# Shift_Register_Test_Board.net
KiCad netlist of a schematic drawn in Altium Designer
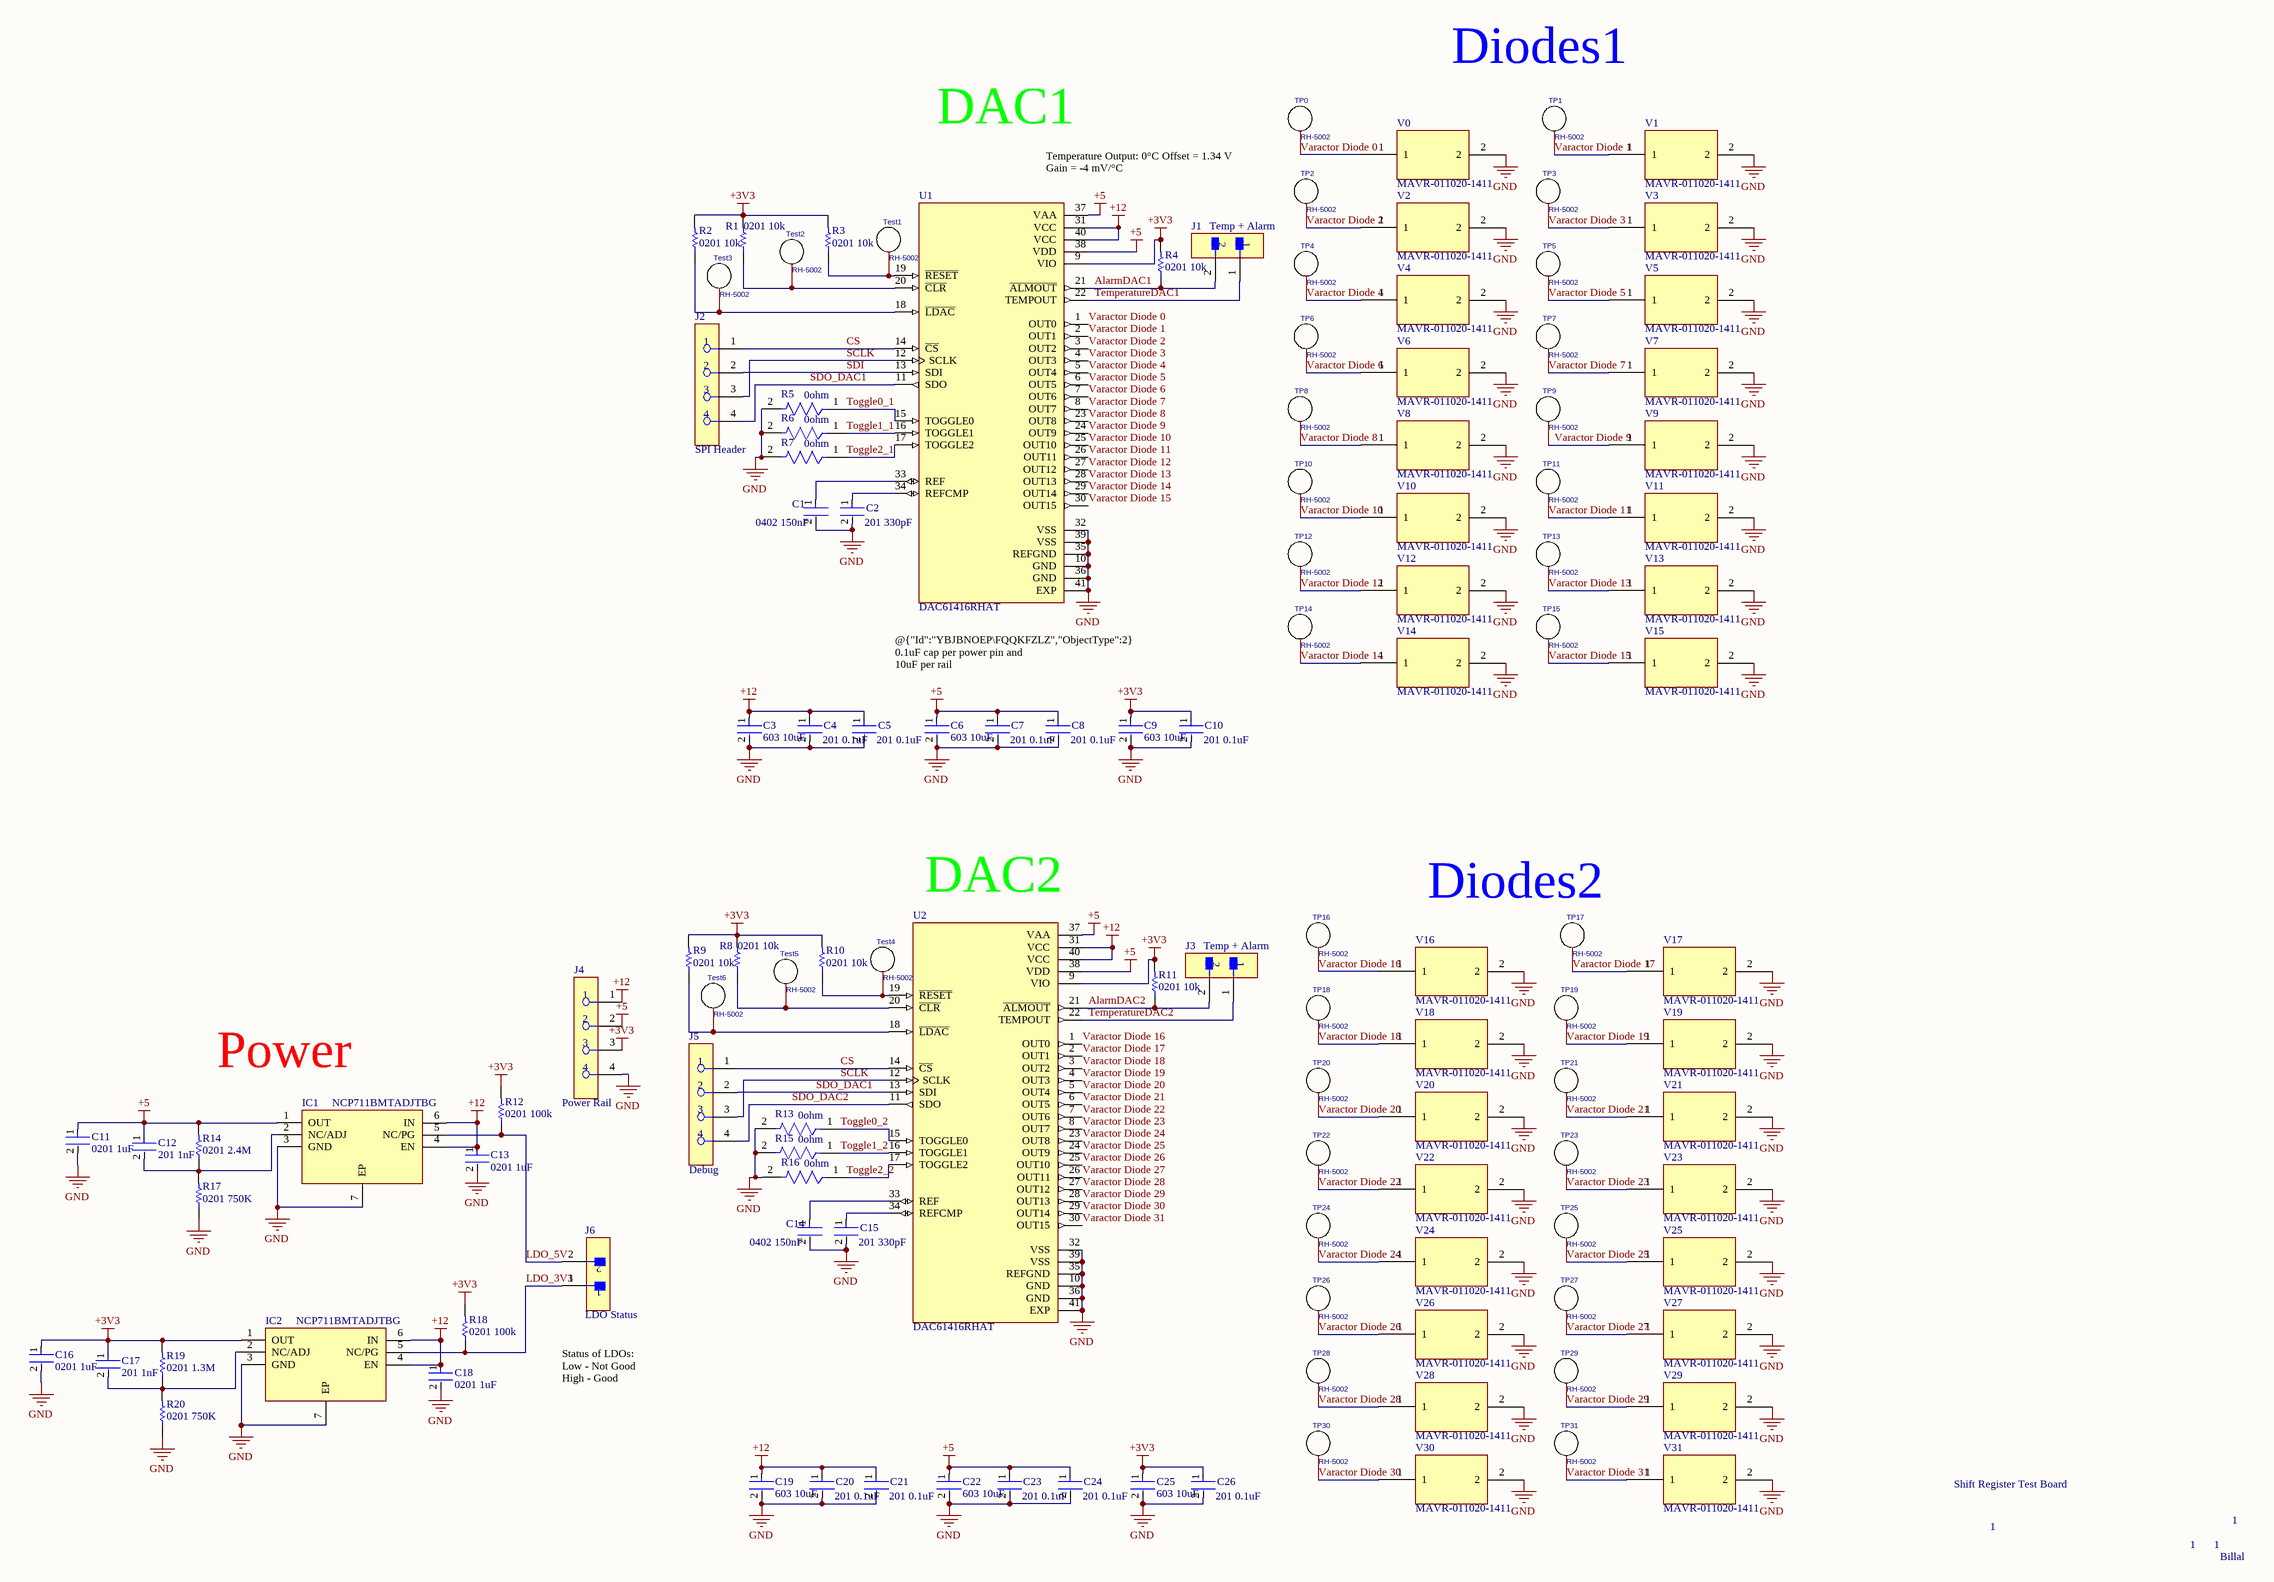
[diagram p0: Shift Register Test Board.SchDoc]

(export (version "E")
  (design (tool "Eeschema 10.0.6"))
  (components
    (comp (ref "C1")
      (value "0402 150nF")
      (footprint "FP-GRM155-0_1-IPC_C")
      (description "C5448879")
      (libsource (lib "Altium Content Vault") (part "11868f565c42a9108669ba33697ecf6"))
    )
    (comp (ref "C2")
      (value "201 330pF")
      (footprint "FP-GRM033-0_09-IPC_A")
      (description "C3899460")
      (fields (field (name "TOLERANCE") "20%"))
      (libsource (lib "Altium Content Vault") (part "02cd4be3c70576c341d710602a673aa"))
    )
    (comp (ref "C3")
      (value "603 10uF")
      (footprint "FP-C0603C106M8PACTU-MFG")
      (description "C194427")
      (libsource (lib "Altium Content Vault") (part "02cd4be3c70576c341d710602a673aa"))
    )
    (comp (ref "C4")
      (value "201 0.1uF")
      (footprint "FP-GRM033-0_09-IPC_A")
      (description "C181043")
      (fields (field (name "TOLERANCE") "20%"))
      (libsource (lib "Altium Content Vault") (part "02cd4be3c70576c341d710602a673aa"))
    )
    (comp (ref "C5")
      (value "201 0.1uF")
      (footprint "FP-GRM033-0_09-IPC_A")
      (description "C181043")
      (fields (field (name "TOLERANCE") "20%"))
      (libsource (lib "Altium Content Vault") (part "02cd4be3c70576c341d710602a673aa"))
    )
    (comp (ref "C6")
      (value "603 10uF")
      (footprint "FP-C0603C106M8PACTU-MFG")
      (description "C194427")
      (libsource (lib "Altium Content Vault") (part "02cd4be3c70576c341d710602a673aa"))
    )
    (comp (ref "C7")
      (value "201 0.1uF")
      (footprint "FP-GRM033-0_09-IPC_A")
      (description "C181043")
      (fields (field (name "TOLERANCE") "20%"))
      (libsource (lib "Altium Content Vault") (part "02cd4be3c70576c341d710602a673aa"))
    )
    (comp (ref "C8")
      (value "201 0.1uF")
      (footprint "FP-GRM033-0_09-IPC_A")
      (description "C181043")
      (fields (field (name "TOLERANCE") "20%"))
      (libsource (lib "Altium Content Vault") (part "02cd4be3c70576c341d710602a673aa"))
    )
    (comp (ref "C9")
      (value "603 10uF")
      (footprint "FP-C0603C106M8PACTU-MFG")
      (description "C194427")
      (libsource (lib "Altium Content Vault") (part "02cd4be3c70576c341d710602a673aa"))
    )
    (comp (ref "C10")
      (value "201 0.1uF")
      (footprint "FP-GRM033-0_09-IPC_A")
      (description "C181043")
      (fields (field (name "TOLERANCE") "20%"))
      (libsource (lib "Altium Content Vault") (part "02cd4be3c70576c341d710602a673aa"))
    )
    (comp (ref "C11")
      (value "0201 1uF")
      (footprint "FP-GRM033-0_09-IPC_A")
      (description "C335102")
      (fields (field (name "TOLERANCE") "20%"))
      (libsource (lib "Altium Content Vault") (part "02cd4be3c70576c341d710602a673aa"))
    )
    (comp (ref "C12")
      (value "201 1nF")
      (footprint "FP-GRM033-0_09-IPC_A")
      (description "C85934")
      (fields (field (name "TOLERANCE") "20%"))
      (libsource (lib "Altium Content Vault") (part "02cd4be3c70576c341d710602a673aa"))
    )
    (comp (ref "C13")
      (value "0201 1uF")
      (footprint "FP-GRM033-0_09-IPC_A")
      (description "C335102")
      (fields (field (name "TOLERANCE") "20%"))
      (libsource (lib "Altium Content Vault") (part "02cd4be3c70576c341d710602a673aa"))
    )
    (comp (ref "C14")
      (value "0402 150nF")
      (footprint "FP-GRM155-0_1-IPC_C")
      (description "C5448879")
      (libsource (lib "Altium Content Vault") (part "11868f565c42a9108669ba33697ecf6"))
    )
    (comp (ref "C15")
      (value "201 330pF")
      (footprint "FP-GRM033-0_09-IPC_A")
      (description "C3899460")
      (fields (field (name "TOLERANCE") "20%"))
      (libsource (lib "Altium Content Vault") (part "02cd4be3c70576c341d710602a673aa"))
    )
    (comp (ref "C16")
      (value "0201 1uF")
      (footprint "FP-GRM033-0_09-IPC_A")
      (description "C335102")
      (fields (field (name "TOLERANCE") "20%"))
      (libsource (lib "Altium Content Vault") (part "02cd4be3c70576c341d710602a673aa"))
    )
    (comp (ref "C17")
      (value "201 1nF")
      (footprint "FP-GRM033-0_09-IPC_A")
      (description "C85934")
      (fields (field (name "TOLERANCE") "20%"))
      (libsource (lib "Altium Content Vault") (part "02cd4be3c70576c341d710602a673aa"))
    )
    (comp (ref "C18")
      (value "0201 1uF")
      (footprint "FP-GRM033-0_09-IPC_A")
      (description "C335102")
      (fields (field (name "TOLERANCE") "20%"))
      (libsource (lib "Altium Content Vault") (part "02cd4be3c70576c341d710602a673aa"))
    )
    (comp (ref "C19")
      (value "603 10uF")
      (footprint "FP-C0603C106M8PACTU-MFG")
      (description "C194427")
      (libsource (lib "Altium Content Vault") (part "02cd4be3c70576c341d710602a673aa"))
    )
    (comp (ref "C20")
      (value "201 0.1uF")
      (footprint "FP-GRM033-0_09-IPC_A")
      (description "C181043")
      (fields (field (name "TOLERANCE") "20%"))
      (libsource (lib "Altium Content Vault") (part "02cd4be3c70576c341d710602a673aa"))
    )
    (comp (ref "C21")
      (value "201 0.1uF")
      (footprint "FP-GRM033-0_09-IPC_A")
      (description "C181043")
      (fields (field (name "TOLERANCE") "20%"))
      (libsource (lib "Altium Content Vault") (part "02cd4be3c70576c341d710602a673aa"))
    )
    (comp (ref "C22")
      (value "603 10uF")
      (footprint "FP-C0603C106M8PACTU-MFG")
      (description "C194427")
      (libsource (lib "Altium Content Vault") (part "02cd4be3c70576c341d710602a673aa"))
    )
    (comp (ref "C23")
      (value "201 0.1uF")
      (footprint "FP-GRM033-0_09-IPC_A")
      (description "C181043")
      (fields (field (name "TOLERANCE") "20%"))
      (libsource (lib "Altium Content Vault") (part "02cd4be3c70576c341d710602a673aa"))
    )
    (comp (ref "C24")
      (value "201 0.1uF")
      (footprint "FP-GRM033-0_09-IPC_A")
      (description "C181043")
      (fields (field (name "TOLERANCE") "20%"))
      (libsource (lib "Altium Content Vault") (part "02cd4be3c70576c341d710602a673aa"))
    )
    (comp (ref "C25")
      (value "603 10uF")
      (footprint "FP-C0603C106M8PACTU-MFG")
      (description "C194427")
      (libsource (lib "Altium Content Vault") (part "02cd4be3c70576c341d710602a673aa"))
    )
    (comp (ref "C26")
      (value "201 0.1uF")
      (footprint "FP-GRM033-0_09-IPC_A")
      (description "C181043")
      (fields (field (name "TOLERANCE") "20%"))
      (libsource (lib "Altium Content Vault") (part "02cd4be3c70576c341d710602a673aa"))
    )
    (comp (ref "IC1")
      (value "NCP711BMTADJTBG")
      (footprint "SamacSys:SON65P200X200X80-7N")
      (description "C893333")
      (fields (field (name "MOUSER PART NUMBER") "863-NCP711BMTADJTBG"))
      (libsource (lib "*") (part "NCP711BMTADJTBG"))
    )
    (comp (ref "IC2")
      (value "NCP711BMTADJTBG")
      (footprint "SamacSys:SON65P200X200X80-7N")
      (description "C893333")
      (fields (field (name "MOUSER PART NUMBER") "863-NCP711BMTADJTBG"))
      (libsource (lib "*") (part "NCP711BMTADJTBG"))
    )
    (comp (ref "J1")
      (value "Temp + Alarm")
      (footprint "FP-TSW-102-12-T-S-MFG")
      (description "CONN HEADER VERT 2POS 2.54MM")
      (libsource (lib "Altium Content Vault") (part "3bc925449376181038e59eaffc5286c"))
    )
    (comp (ref "J2")
      (value "SPI Header")
      (footprint "FP-315-43-104-41-003000-MFG")
      (description "315-43-104-41-003000 4 Position Receptacle Connector 0.100 (2.54mm) Through Hole Gold\"")
      (libsource (lib "Altium Content Vault") (part "315-43-104-41-003000"))
    )
    (comp (ref "J3")
      (value "Temp + Alarm")
      (footprint "FP-TSW-102-12-T-S-MFG")
      (description "CONN HEADER VERT 2POS 2.54MM")
      (libsource (lib "Altium Content Vault") (part "3bc925449376181038e59eaffc5286c"))
    )
    (comp (ref "J4")
      (value "Power Rail")
      (footprint "FP-315-43-104-41-003000-MFG")
      (description "315-43-104-41-003000 4 Position Receptacle Connector 0.100 (2.54mm) Through Hole Gold\"")
      (libsource (lib "Altium Content Vault") (part "315-43-104-41-003000"))
    )
    (comp (ref "J5")
      (value "Debug")
      (footprint "FP-315-43-104-41-003000-MFG")
      (description "315-43-104-41-003000 4 Position Receptacle Connector 0.100 (2.54mm) Through Hole Gold\"")
      (libsource (lib "Altium Content Vault") (part "315-43-104-41-003000"))
    )
    (comp (ref "J6")
      (value "LDO Status")
      (footprint "FP-TSW-102-12-T-S-MFG")
      (description "CONN HEADER VERT 2POS 2.54MM")
      (libsource (lib "") (part "3bc925449376181038e59eaffc5286c_1"))
    )
    (comp (ref "R1")
      (value "0201 10k")
      (footprint "RESC0603X26X15LL03T05")
      (description "C106225")
      (fields
        (field (name "MANUFACTURER") "TE Connectivity / AMP")
        (field (name "PART NUMBER") "CRG0201F10K")
      )
      (libsource (lib "Altium Content Vault") (part "RES"))
    )
    (comp (ref "R2")
      (value "0201 10k")
      (footprint "RESC0603X26X15LL03T05")
      (description "C106225")
      (fields
        (field (name "MANUFACTURER") "TE Connectivity / AMP")
        (field (name "PART NUMBER") "CRG0201F10K")
      )
      (libsource (lib "Altium Content Vault") (part "RES"))
    )
    (comp (ref "R3")
      (value "0201 10k")
      (footprint "RESC0603X26X15LL03T05")
      (description "C106225")
      (fields
        (field (name "MANUFACTURER") "TE Connectivity / AMP")
        (field (name "PART NUMBER") "CRG0201F10K")
      )
      (libsource (lib "Altium Content Vault") (part "RES"))
    )
    (comp (ref "R4")
      (value "0201 10k")
      (footprint "RESC0603X26X15LL03T05")
      (description "C106225")
      (fields
        (field (name "MANUFACTURER") "TE Connectivity / AMP")
        (field (name "PART NUMBER") "CRG0201F10K")
      )
      (libsource (lib "Altium Content Vault") (part "RES"))
    )
    (comp (ref "R5")
      (value "0ohm")
      (footprint "FP-HCJ1206-MFG")
      (description "C17888")
      (libsource (lib "Altium Content Vault") (part "1029c3af85768c4190bb7ad29bc67b5"))
    )
    (comp (ref "R6")
      (value "0ohm")
      (footprint "FP-HCJ1206-MFG")
      (description "C17888")
      (libsource (lib "Altium Content Vault") (part "1029c3af85768c4190bb7ad29bc67b5"))
    )
    (comp (ref "R7")
      (value "0ohm")
      (footprint "FP-HCJ1206-MFG")
      (description "C17888")
      (libsource (lib "Altium Content Vault") (part "1029c3af85768c4190bb7ad29bc67b5"))
    )
    (comp (ref "R8")
      (value "0201 10k")
      (footprint "RESC0603X26X15LL03T05")
      (description "C106225")
      (fields
        (field (name "MANUFACTURER") "TE Connectivity / AMP")
        (field (name "PART NUMBER") "CRG0201F10K")
      )
      (libsource (lib "Altium Content Vault") (part "RES"))
    )
    (comp (ref "R9")
      (value "0201 10k")
      (footprint "RESC0603X26X15LL03T05")
      (description "C106225")
      (fields
        (field (name "MANUFACTURER") "TE Connectivity / AMP")
        (field (name "PART NUMBER") "CRG0201F10K")
      )
      (libsource (lib "Altium Content Vault") (part "RES"))
    )
    (comp (ref "R10")
      (value "0201 10k")
      (footprint "RESC0603X26X15LL03T05")
      (description "C106225")
      (fields
        (field (name "MANUFACTURER") "TE Connectivity / AMP")
        (field (name "PART NUMBER") "CRG0201F10K")
      )
      (libsource (lib "Altium Content Vault") (part "RES"))
    )
    (comp (ref "R11")
      (value "0201 10k")
      (footprint "RESC0603X26X15LL03T05")
      (description "C106225")
      (fields
        (field (name "MANUFACTURER") "TE Connectivity / AMP")
        (field (name "PART NUMBER") "CRG0201F10K")
      )
      (libsource (lib "Altium Content Vault") (part "RES"))
    )
    (comp (ref "R12")
      (value "0201 100k")
      (footprint "RESC0603X26X15LL03T05")
      (description "C106224")
      (fields
        (field (name "MANUFACTURER") "TE Connectivity / AMP")
        (field (name "PART NUMBER") "CRG0201F10K")
      )
      (libsource (lib "Altium Content Vault") (part "RES"))
    )
    (comp (ref "R13")
      (value "0ohm")
      (footprint "FP-HCJ1206-MFG")
      (description "C17888")
      (libsource (lib "Altium Content Vault") (part "1029c3af85768c4190bb7ad29bc67b5"))
    )
    (comp (ref "R14")
      (value "0201 2.4M")
      (footprint "RESC0603X26X15LL03T05")
      (description "C423649")
      (fields
        (field (name "MANUFACTURER") "TE Connectivity / AMP")
        (field (name "PART NUMBER") "CRG0201F10K")
      )
      (libsource (lib "Altium Content Vault") (part "RES"))
    )
    (comp (ref "R15")
      (value "0ohm")
      (footprint "FP-HCJ1206-MFG")
      (description "C17888")
      (libsource (lib "Altium Content Vault") (part "1029c3af85768c4190bb7ad29bc67b5"))
    )
    (comp (ref "R16")
      (value "0ohm")
      (footprint "FP-HCJ1206-MFG")
      (description "C17888")
      (libsource (lib "Altium Content Vault") (part "1029c3af85768c4190bb7ad29bc67b5"))
    )
    (comp (ref "R17")
      (value "0201 750K")
      (footprint "RESC0603X26X15LL03T05")
      (description "C158358")
      (fields
        (field (name "MANUFACTURER") "TE Connectivity / AMP")
        (field (name "PART NUMBER") "CRG0201F10K")
      )
      (libsource (lib "Altium Content Vault") (part "RES"))
    )
    (comp (ref "R18")
      (value "0201 100k")
      (footprint "RESC0603X26X15LL03T05")
      (description "C106224")
      (fields
        (field (name "MANUFACTURER") "TE Connectivity / AMP")
        (field (name "PART NUMBER") "CRG0201F10K")
      )
      (libsource (lib "Altium Content Vault") (part "RES"))
    )
    (comp (ref "R19")
      (value "0201 1.3M")
      (footprint "RESC0603X26X15LL03T05")
      (description "C307090")
      (fields
        (field (name "MANUFACTURER") "TE Connectivity / AMP")
        (field (name "PART NUMBER") "CRG0201F10K")
      )
      (libsource (lib "Altium Content Vault") (part "RES"))
    )
    (comp (ref "R20")
      (value "0201 750K")
      (footprint "RESC0603X26X15LL03T05")
      (description "C158358")
      (fields
        (field (name "MANUFACTURER") "TE Connectivity / AMP")
        (field (name "PART NUMBER") "CRG0201F10K")
      )
      (libsource (lib "Altium Content Vault") (part "RES"))
    )
    (comp (ref "Test1")
      (value "RH-5002")
      (footprint "TESTPOINT-TH_BD2.5-D1.2_RH-5002")
      (description "C5199802")
      (fields (field (name "MANUFACTURER") "荣和"))
      (libsource (lib "mmWave_RIS_Lumo") (part "RH-5002"))
    )
    (comp (ref "Test2")
      (value "RH-5002")
      (footprint "TESTPOINT-TH_BD2.5-D1.2_RH-5002")
      (description "C5199802")
      (fields (field (name "MANUFACTURER") "荣和"))
      (libsource (lib "mmWave_RIS_Lumo") (part "RH-5002"))
    )
    (comp (ref "Test3")
      (value "RH-5002")
      (footprint "TESTPOINT-TH_BD2.5-D1.2_RH-5002")
      (description "C5199802")
      (fields (field (name "MANUFACTURER") "荣和"))
      (libsource (lib "mmWave_RIS_Lumo") (part "RH-5002"))
    )
    (comp (ref "Test4")
      (value "RH-5002")
      (footprint "TESTPOINT-TH_BD2.5-D1.2_RH-5002")
      (description "C5199802")
      (fields (field (name "MANUFACTURER") "荣和"))
      (libsource (lib "mmWave_RIS_Lumo") (part "RH-5002"))
    )
    (comp (ref "Test5")
      (value "RH-5002")
      (footprint "TESTPOINT-TH_BD2.5-D1.2_RH-5002")
      (description "C5199802")
      (fields (field (name "MANUFACTURER") "荣和"))
      (libsource (lib "mmWave_RIS_Lumo") (part "RH-5002"))
    )
    (comp (ref "Test6")
      (value "RH-5002")
      (footprint "TESTPOINT-TH_BD2.5-D1.2_RH-5002")
      (description "C5199802")
      (fields (field (name "MANUFACTURER") "荣和"))
      (libsource (lib "mmWave_RIS_Lumo") (part "RH-5002"))
    )
    (comp (ref "TP0")
      (value "RH-5002")
      (footprint "TESTPOINT-TH_BD2.5-D1.2_RH-5002")
      (description "C5199802")
      (fields (field (name "MANUFACTURER") "荣和"))
      (libsource (lib "mmWave_RIS_Lumo") (part "RH-5002"))
    )
    (comp (ref "TP1")
      (value "RH-5002")
      (footprint "TESTPOINT-TH_BD2.5-D1.2_RH-5002")
      (description "C5199802")
      (fields (field (name "MANUFACTURER") "荣和"))
      (libsource (lib "mmWave_RIS_Lumo") (part "RH-5002"))
    )
    (comp (ref "TP2")
      (value "RH-5002")
      (footprint "TESTPOINT-TH_BD2.5-D1.2_RH-5002")
      (description "C5199802")
      (fields (field (name "MANUFACTURER") "荣和"))
      (libsource (lib "mmWave_RIS_Lumo") (part "RH-5002"))
    )
    (comp (ref "TP3")
      (value "RH-5002")
      (footprint "TESTPOINT-TH_BD2.5-D1.2_RH-5002")
      (description "C5199802")
      (fields (field (name "MANUFACTURER") "荣和"))
      (libsource (lib "mmWave_RIS_Lumo") (part "RH-5002"))
    )
    (comp (ref "TP4")
      (value "RH-5002")
      (footprint "TESTPOINT-TH_BD2.5-D1.2_RH-5002")
      (description "C5199802")
      (fields (field (name "MANUFACTURER") "荣和"))
      (libsource (lib "mmWave_RIS_Lumo") (part "RH-5002"))
    )
    (comp (ref "TP5")
      (value "RH-5002")
      (footprint "TESTPOINT-TH_BD2.5-D1.2_RH-5002")
      (description "C5199802")
      (fields (field (name "MANUFACTURER") "荣和"))
      (libsource (lib "mmWave_RIS_Lumo") (part "RH-5002"))
    )
    (comp (ref "TP6")
      (value "RH-5002")
      (footprint "TESTPOINT-TH_BD2.5-D1.2_RH-5002")
      (description "C5199802")
      (fields (field (name "MANUFACTURER") "荣和"))
      (libsource (lib "mmWave_RIS_Lumo") (part "RH-5002"))
    )
    (comp (ref "TP7")
      (value "RH-5002")
      (footprint "TESTPOINT-TH_BD2.5-D1.2_RH-5002")
      (description "C5199802")
      (fields (field (name "MANUFACTURER") "荣和"))
      (libsource (lib "mmWave_RIS_Lumo") (part "RH-5002"))
    )
    (comp (ref "TP8")
      (value "RH-5002")
      (footprint "TESTPOINT-TH_BD2.5-D1.2_RH-5002")
      (description "C5199802")
      (fields (field (name "MANUFACTURER") "荣和"))
      (libsource (lib "mmWave_RIS_Lumo") (part "RH-5002"))
    )
    (comp (ref "TP9")
      (value "RH-5002")
      (footprint "TESTPOINT-TH_BD2.5-D1.2_RH-5002")
      (description "C5199802")
      (fields (field (name "MANUFACTURER") "荣和"))
      (libsource (lib "mmWave_RIS_Lumo") (part "RH-5002"))
    )
    (comp (ref "TP10")
      (value "RH-5002")
      (footprint "TESTPOINT-TH_BD2.5-D1.2_RH-5002")
      (description "C5199802")
      (fields (field (name "MANUFACTURER") "荣和"))
      (libsource (lib "mmWave_RIS_Lumo") (part "RH-5002"))
    )
    (comp (ref "TP11")
      (value "RH-5002")
      (footprint "TESTPOINT-TH_BD2.5-D1.2_RH-5002")
      (description "C5199802")
      (fields (field (name "MANUFACTURER") "荣和"))
      (libsource (lib "mmWave_RIS_Lumo") (part "RH-5002"))
    )
    (comp (ref "TP12")
      (value "RH-5002")
      (footprint "TESTPOINT-TH_BD2.5-D1.2_RH-5002")
      (description "C5199802")
      (fields (field (name "MANUFACTURER") "荣和"))
      (libsource (lib "mmWave_RIS_Lumo") (part "RH-5002"))
    )
    (comp (ref "TP13")
      (value "RH-5002")
      (footprint "TESTPOINT-TH_BD2.5-D1.2_RH-5002")
      (description "C5199802")
      (fields (field (name "MANUFACTURER") "荣和"))
      (libsource (lib "mmWave_RIS_Lumo") (part "RH-5002"))
    )
    (comp (ref "TP14")
      (value "RH-5002")
      (footprint "TESTPOINT-TH_BD2.5-D1.2_RH-5002")
      (description "C5199802")
      (fields (field (name "MANUFACTURER") "荣和"))
      (libsource (lib "mmWave_RIS_Lumo") (part "RH-5002"))
    )
    (comp (ref "TP15")
      (value "RH-5002")
      (footprint "TESTPOINT-TH_BD2.5-D1.2_RH-5002")
      (description "C5199802")
      (fields (field (name "MANUFACTURER") "荣和"))
      (libsource (lib "mmWave_RIS_Lumo") (part "RH-5002"))
    )
    (comp (ref "TP16")
      (value "RH-5002")
      (footprint "TESTPOINT-TH_BD2.5-D1.2_RH-5002")
      (description "C5199802")
      (fields (field (name "MANUFACTURER") "荣和"))
      (libsource (lib "mmWave_RIS_Lumo") (part "RH-5002"))
    )
    (comp (ref "TP17")
      (value "RH-5002")
      (footprint "TESTPOINT-TH_BD2.5-D1.2_RH-5002")
      (description "C5199802")
      (fields (field (name "MANUFACTURER") "荣和"))
      (libsource (lib "mmWave_RIS_Lumo") (part "RH-5002"))
    )
    (comp (ref "TP18")
      (value "RH-5002")
      (footprint "TESTPOINT-TH_BD2.5-D1.2_RH-5002")
      (description "C5199802")
      (fields (field (name "MANUFACTURER") "荣和"))
      (libsource (lib "mmWave_RIS_Lumo") (part "RH-5002"))
    )
    (comp (ref "TP19")
      (value "RH-5002")
      (footprint "TESTPOINT-TH_BD2.5-D1.2_RH-5002")
      (description "C5199802")
      (fields (field (name "MANUFACTURER") "荣和"))
      (libsource (lib "mmWave_RIS_Lumo") (part "RH-5002"))
    )
    (comp (ref "TP20")
      (value "RH-5002")
      (footprint "TESTPOINT-TH_BD2.5-D1.2_RH-5002")
      (description "C5199802")
      (fields (field (name "MANUFACTURER") "荣和"))
      (libsource (lib "mmWave_RIS_Lumo") (part "RH-5002"))
    )
    (comp (ref "TP21")
      (value "RH-5002")
      (footprint "TESTPOINT-TH_BD2.5-D1.2_RH-5002")
      (description "C5199802")
      (fields (field (name "MANUFACTURER") "荣和"))
      (libsource (lib "mmWave_RIS_Lumo") (part "RH-5002"))
    )
    (comp (ref "TP22")
      (value "RH-5002")
      (footprint "TESTPOINT-TH_BD2.5-D1.2_RH-5002")
      (description "C5199802")
      (fields (field (name "MANUFACTURER") "荣和"))
      (libsource (lib "mmWave_RIS_Lumo") (part "RH-5002"))
    )
    (comp (ref "TP23")
      (value "RH-5002")
      (footprint "TESTPOINT-TH_BD2.5-D1.2_RH-5002")
      (description "C5199802")
      (fields (field (name "MANUFACTURER") "荣和"))
      (libsource (lib "mmWave_RIS_Lumo") (part "RH-5002"))
    )
    (comp (ref "TP24")
      (value "RH-5002")
      (footprint "TESTPOINT-TH_BD2.5-D1.2_RH-5002")
      (description "C5199802")
      (fields (field (name "MANUFACTURER") "荣和"))
      (libsource (lib "mmWave_RIS_Lumo") (part "RH-5002"))
    )
    (comp (ref "TP25")
      (value "RH-5002")
      (footprint "TESTPOINT-TH_BD2.5-D1.2_RH-5002")
      (description "C5199802")
      (fields (field (name "MANUFACTURER") "荣和"))
      (libsource (lib "mmWave_RIS_Lumo") (part "RH-5002"))
    )
    (comp (ref "TP26")
      (value "RH-5002")
      (footprint "TESTPOINT-TH_BD2.5-D1.2_RH-5002")
      (description "C5199802")
      (fields (field (name "MANUFACTURER") "荣和"))
      (libsource (lib "mmWave_RIS_Lumo") (part "RH-5002"))
    )
    (comp (ref "TP27")
      (value "RH-5002")
      (footprint "TESTPOINT-TH_BD2.5-D1.2_RH-5002")
      (description "C5199802")
      (fields (field (name "MANUFACTURER") "荣和"))
      (libsource (lib "mmWave_RIS_Lumo") (part "RH-5002"))
    )
    (comp (ref "TP28")
      (value "RH-5002")
      (footprint "TESTPOINT-TH_BD2.5-D1.2_RH-5002")
      (description "C5199802")
      (fields (field (name "MANUFACTURER") "荣和"))
      (libsource (lib "mmWave_RIS_Lumo") (part "RH-5002"))
    )
    (comp (ref "TP29")
      (value "RH-5002")
      (footprint "TESTPOINT-TH_BD2.5-D1.2_RH-5002")
      (description "C5199802")
      (fields (field (name "MANUFACTURER") "荣和"))
      (libsource (lib "mmWave_RIS_Lumo") (part "RH-5002"))
    )
    (comp (ref "TP30")
      (value "RH-5002")
      (footprint "TESTPOINT-TH_BD2.5-D1.2_RH-5002")
      (description "C5199802")
      (fields (field (name "MANUFACTURER") "荣和"))
      (libsource (lib "mmWave_RIS_Lumo") (part "RH-5002"))
    )
    (comp (ref "TP31")
      (value "RH-5002")
      (footprint "TESTPOINT-TH_BD2.5-D1.2_RH-5002")
      (description "C5199802")
      (fields (field (name "MANUFACTURER") "荣和"))
      (libsource (lib "mmWave_RIS_Lumo") (part "RH-5002"))
    )
    (comp (ref "U1")
      (value "DAC61416RHAT")
      (footprint "DAC61416RHAT")
      (libsource (lib "mmWave_RIS_Lumo") (part "DAC61416RHAT"))
    )
    (comp (ref "U2")
      (value "DAC61416RHAT")
      (footprint "DAC61416RHAT")
      (libsource (lib "mmWave_RIS_Lumo") (part "DAC61416RHAT"))
    )
    (comp (ref "V0")
      (value "MAVR-011020-1411")
      (footprint "MAVR-011020-1411")
      (libsource (lib "mmWave_RIS_Lumo") (part "MAVR-011020-1411"))
    )
    (comp (ref "V1")
      (value "MAVR-011020-1411")
      (footprint "MAVR-011020-1411")
      (libsource (lib "mmWave_RIS_Lumo") (part "MAVR-011020-1411"))
    )
    (comp (ref "V2")
      (value "MAVR-011020-1411")
      (footprint "MAVR-011020-1411")
      (libsource (lib "mmWave_RIS_Lumo") (part "MAVR-011020-1411"))
    )
    (comp (ref "V3")
      (value "MAVR-011020-1411")
      (footprint "MAVR-011020-1411")
      (libsource (lib "mmWave_RIS_Lumo") (part "MAVR-011020-1411"))
    )
    (comp (ref "V4")
      (value "MAVR-011020-1411")
      (footprint "MAVR-011020-1411")
      (libsource (lib "mmWave_RIS_Lumo") (part "MAVR-011020-1411"))
    )
    (comp (ref "V5")
      (value "MAVR-011020-1411")
      (footprint "MAVR-011020-1411")
      (libsource (lib "mmWave_RIS_Lumo") (part "MAVR-011020-1411"))
    )
    (comp (ref "V6")
      (value "MAVR-011020-1411")
      (footprint "MAVR-011020-1411")
      (libsource (lib "mmWave_RIS_Lumo") (part "MAVR-011020-1411"))
    )
    (comp (ref "V7")
      (value "MAVR-011020-1411")
      (footprint "MAVR-011020-1411")
      (libsource (lib "mmWave_RIS_Lumo") (part "MAVR-011020-1411"))
    )
    (comp (ref "V8")
      (value "MAVR-011020-1411")
      (footprint "MAVR-011020-1411")
      (libsource (lib "mmWave_RIS_Lumo") (part "MAVR-011020-1411"))
    )
    (comp (ref "V9")
      (value "MAVR-011020-1411")
      (footprint "MAVR-011020-1411")
      (libsource (lib "mmWave_RIS_Lumo") (part "MAVR-011020-1411"))
    )
    (comp (ref "V10")
      (value "MAVR-011020-1411")
      (footprint "MAVR-011020-1411")
      (libsource (lib "mmWave_RIS_Lumo") (part "MAVR-011020-1411"))
    )
    (comp (ref "V11")
      (value "MAVR-011020-1411")
      (footprint "MAVR-011020-1411")
      (libsource (lib "mmWave_RIS_Lumo") (part "MAVR-011020-1411"))
    )
    (comp (ref "V12")
      (value "MAVR-011020-1411")
      (footprint "MAVR-011020-1411")
      (libsource (lib "mmWave_RIS_Lumo") (part "MAVR-011020-1411"))
    )
    (comp (ref "V13")
      (value "MAVR-011020-1411")
      (footprint "MAVR-011020-1411")
      (libsource (lib "mmWave_RIS_Lumo") (part "MAVR-011020-1411"))
    )
    (comp (ref "V14")
      (value "MAVR-011020-1411")
      (footprint "MAVR-011020-1411")
      (libsource (lib "mmWave_RIS_Lumo") (part "MAVR-011020-1411"))
    )
    (comp (ref "V15")
      (value "MAVR-011020-1411")
      (footprint "MAVR-011020-1411")
      (libsource (lib "mmWave_RIS_Lumo") (part "MAVR-011020-1411"))
    )
    (comp (ref "V16")
      (value "MAVR-011020-1411")
      (footprint "MAVR-011020-1411")
      (libsource (lib "mmWave_RIS_Lumo") (part "MAVR-011020-1411"))
    )
    (comp (ref "V17")
      (value "MAVR-011020-1411")
      (footprint "MAVR-011020-1411")
      (libsource (lib "mmWave_RIS_Lumo") (part "MAVR-011020-1411"))
    )
    (comp (ref "V18")
      (value "MAVR-011020-1411")
      (footprint "MAVR-011020-1411")
      (libsource (lib "mmWave_RIS_Lumo") (part "MAVR-011020-1411"))
    )
    (comp (ref "V19")
      (value "MAVR-011020-1411")
      (footprint "MAVR-011020-1411")
      (libsource (lib "mmWave_RIS_Lumo") (part "MAVR-011020-1411"))
    )
    (comp (ref "V20")
      (value "MAVR-011020-1411")
      (footprint "MAVR-011020-1411")
      (libsource (lib "mmWave_RIS_Lumo") (part "MAVR-011020-1411"))
    )
    (comp (ref "V21")
      (value "MAVR-011020-1411")
      (footprint "MAVR-011020-1411")
      (libsource (lib "mmWave_RIS_Lumo") (part "MAVR-011020-1411"))
    )
    (comp (ref "V22")
      (value "MAVR-011020-1411")
      (footprint "MAVR-011020-1411")
      (libsource (lib "mmWave_RIS_Lumo") (part "MAVR-011020-1411"))
    )
    (comp (ref "V23")
      (value "MAVR-011020-1411")
      (footprint "MAVR-011020-1411")
      (libsource (lib "mmWave_RIS_Lumo") (part "MAVR-011020-1411"))
    )
    (comp (ref "V24")
      (value "MAVR-011020-1411")
      (footprint "MAVR-011020-1411")
      (libsource (lib "mmWave_RIS_Lumo") (part "MAVR-011020-1411"))
    )
    (comp (ref "V25")
      (value "MAVR-011020-1411")
      (footprint "MAVR-011020-1411")
      (libsource (lib "mmWave_RIS_Lumo") (part "MAVR-011020-1411"))
    )
    (comp (ref "V26")
      (value "MAVR-011020-1411")
      (footprint "MAVR-011020-1411")
      (libsource (lib "mmWave_RIS_Lumo") (part "MAVR-011020-1411"))
    )
    (comp (ref "V27")
      (value "MAVR-011020-1411")
      (footprint "MAVR-011020-1411")
      (libsource (lib "mmWave_RIS_Lumo") (part "MAVR-011020-1411"))
    )
    (comp (ref "V28")
      (value "MAVR-011020-1411")
      (footprint "MAVR-011020-1411")
      (libsource (lib "mmWave_RIS_Lumo") (part "MAVR-011020-1411"))
    )
    (comp (ref "V29")
      (value "MAVR-011020-1411")
      (footprint "MAVR-011020-1411")
      (libsource (lib "mmWave_RIS_Lumo") (part "MAVR-011020-1411"))
    )
    (comp (ref "V30")
      (value "MAVR-011020-1411")
      (footprint "MAVR-011020-1411")
      (libsource (lib "mmWave_RIS_Lumo") (part "MAVR-011020-1411"))
    )
    (comp (ref "V31")
      (value "MAVR-011020-1411")
      (footprint "MAVR-011020-1411")
      (libsource (lib "mmWave_RIS_Lumo") (part "MAVR-011020-1411"))
    )
  )
  (nets
    (net (code "1") (name "+3V3") (class "Default")
      (node (ref "C10") (pin "1") (pinfunction "1_1") (pintype "passive"))
      (node (ref "C16") (pin "1") (pinfunction "1_1") (pintype "passive"))
      (node (ref "C17") (pin "1") (pinfunction "1_1") (pintype "passive"))
      (node (ref "C25") (pin "1") (pinfunction "1_1") (pintype "passive"))
      (node (ref "C26") (pin "1") (pinfunction "1_1") (pintype "passive"))
      (node (ref "C9") (pin "1") (pinfunction "1_1") (pintype "passive"))
      (node (ref "IC2") (pin "1") (pinfunction "OUT_1") (pintype "passive"))
      (node (ref "J4") (pin "3") (pinfunction "3_3") (pintype "passive"))
      (node (ref "R1") (pin "2") (pinfunction "2_2") (pintype "passive"))
      (node (ref "R10") (pin "2") (pinfunction "2_2") (pintype "passive"))
      (node (ref "R11") (pin "2") (pinfunction "2_2") (pintype "passive"))
      (node (ref "R12") (pin "2") (pinfunction "2_2") (pintype "passive"))
      (node (ref "R18") (pin "2") (pinfunction "2_2") (pintype "passive"))
      (node (ref "R19") (pin "2") (pinfunction "2_2") (pintype "passive"))
      (node (ref "R2") (pin "2") (pinfunction "2_2") (pintype "passive"))
      (node (ref "R3") (pin "2") (pinfunction "2_2") (pintype "passive"))
      (node (ref "R4") (pin "2") (pinfunction "2_2") (pintype "passive"))
      (node (ref "R8") (pin "2") (pinfunction "2_2") (pintype "passive"))
      (node (ref "R9") (pin "2") (pinfunction "2_2") (pintype "passive"))
      (node (ref "U1") (pin "9") (pinfunction "VIO_9") (pintype "power_in"))
      (node (ref "U2") (pin "9") (pinfunction "VIO_9") (pintype "power_in"))
    )
    (net (code "2") (name "+5") (class "Default")
      (node (ref "C11") (pin "1") (pinfunction "1_1") (pintype "passive"))
      (node (ref "C12") (pin "1") (pinfunction "1_1") (pintype "passive"))
      (node (ref "C22") (pin "1") (pinfunction "1_1") (pintype "passive"))
      (node (ref "C23") (pin "1") (pinfunction "1_1") (pintype "passive"))
      (node (ref "C24") (pin "1") (pinfunction "1_1") (pintype "passive"))
      (node (ref "C6") (pin "1") (pinfunction "1_1") (pintype "passive"))
      (node (ref "C7") (pin "1") (pinfunction "1_1") (pintype "passive"))
      (node (ref "C8") (pin "1") (pinfunction "1_1") (pintype "passive"))
      (node (ref "IC1") (pin "1") (pinfunction "OUT_1") (pintype "passive"))
      (node (ref "J4") (pin "2") (pinfunction "2_2") (pintype "passive"))
      (node (ref "R14") (pin "2") (pinfunction "2_2") (pintype "passive"))
      (node (ref "U1") (pin "37") (pinfunction "VAA_37") (pintype "power_in"))
      (node (ref "U1") (pin "38") (pinfunction "VDD_38") (pintype "power_in"))
      (node (ref "U2") (pin "37") (pinfunction "VAA_37") (pintype "power_in"))
      (node (ref "U2") (pin "38") (pinfunction "VDD_38") (pintype "power_in"))
    )
    (net (code "3") (name "+12") (class "Default")
      (node (ref "C13") (pin "1") (pinfunction "1_1") (pintype "passive"))
      (node (ref "C18") (pin "1") (pinfunction "1_1") (pintype "passive"))
      (node (ref "C19") (pin "1") (pinfunction "1_1") (pintype "passive"))
      (node (ref "C20") (pin "1") (pinfunction "1_1") (pintype "passive"))
      (node (ref "C21") (pin "1") (pinfunction "1_1") (pintype "passive"))
      (node (ref "C3") (pin "1") (pinfunction "1_1") (pintype "passive"))
      (node (ref "C4") (pin "1") (pinfunction "1_1") (pintype "passive"))
      (node (ref "C5") (pin "1") (pinfunction "1_1") (pintype "passive"))
      (node (ref "IC1") (pin "4") (pinfunction "EN_4") (pintype "passive"))
      (node (ref "IC1") (pin "6") (pinfunction "IN_6") (pintype "passive"))
      (node (ref "IC2") (pin "4") (pinfunction "EN_4") (pintype "passive"))
      (node (ref "IC2") (pin "6") (pinfunction "IN_6") (pintype "passive"))
      (node (ref "J4") (pin "1") (pinfunction "1_1") (pintype "passive"))
      (node (ref "U1") (pin "31") (pinfunction "VCC_31") (pintype "power_in"))
      (node (ref "U1") (pin "40") (pinfunction "VCC_40") (pintype "power_in"))
      (node (ref "U2") (pin "31") (pinfunction "VCC_31") (pintype "power_in"))
      (node (ref "U2") (pin "40") (pinfunction "VCC_40") (pintype "power_in"))
    )
    (net (code "4") (name "/AlarmDAC1") (class "Default")
      (node (ref "J1") (pin "2") (pinfunction "2_2") (pintype "passive"))
      (node (ref "R4") (pin "1") (pinfunction "1_1") (pintype "passive"))
      (node (ref "U1") (pin "21") (pinfunction "~{ALMOUT}_21") (pintype "output"))
    )
    (net (code "5") (name "/AlarmDAC2") (class "Default")
      (node (ref "J3") (pin "2") (pinfunction "2_2") (pintype "passive"))
      (node (ref "R11") (pin "1") (pinfunction "1_1") (pintype "passive"))
      (node (ref "U2") (pin "21") (pinfunction "~{ALMOUT}_21") (pintype "output"))
    )
    (net (code "6") (name "/CS") (class "Default")
      (node (ref "J2") (pin "1") (pinfunction "1_1") (pintype "passive"))
      (node (ref "J5") (pin "1") (pinfunction "1_1") (pintype "passive"))
      (node (ref "U1") (pin "14") (pinfunction "~{CS}_14") (pintype "input"))
      (node (ref "U2") (pin "14") (pinfunction "~{CS}_14") (pintype "input"))
    )
    (net (code "7") (name "/LDO_3V3") (class "Default")
      (node (ref "IC2") (pin "5") (pinfunction "NC/PG_5") (pintype "passive"))
      (node (ref "J6") (pin "1") (pinfunction "1_1") (pintype "passive"))
      (node (ref "R18") (pin "1") (pinfunction "1_1") (pintype "passive"))
    )
    (net (code "8") (name "/LDO_5V") (class "Default")
      (node (ref "IC1") (pin "5") (pinfunction "NC/PG_5") (pintype "passive"))
      (node (ref "J6") (pin "2") (pinfunction "2_2") (pintype "passive"))
      (node (ref "R12") (pin "1") (pinfunction "1_1") (pintype "passive"))
    )
    (net (code "9") (name "/SCLK") (class "Default")
      (node (ref "J2") (pin "3") (pinfunction "3_3") (pintype "passive"))
      (node (ref "J5") (pin "3") (pinfunction "3_3") (pintype "passive"))
      (node (ref "U1") (pin "12") (pinfunction "SCLK_12") (pintype "input"))
      (node (ref "U2") (pin "12") (pinfunction "SCLK_12") (pintype "input"))
    )
    (net (code "10") (name "/SDI") (class "Default")
      (node (ref "J2") (pin "2") (pinfunction "2_2") (pintype "passive"))
      (node (ref "U1") (pin "13") (pinfunction "SDI_13") (pintype "input"))
    )
    (net (code "11") (name "/SDO_DAC1") (class "Default")
      (node (ref "J2") (pin "4") (pinfunction "4_4") (pintype "passive"))
      (node (ref "J5") (pin "2") (pinfunction "2_2") (pintype "passive"))
      (node (ref "U1") (pin "11") (pinfunction "SDO_11") (pintype "output"))
      (node (ref "U2") (pin "13") (pinfunction "SDI_13") (pintype "input"))
    )
    (net (code "12") (name "/SDO_DAC2") (class "Default")
      (node (ref "J5") (pin "4") (pinfunction "4_4") (pintype "passive"))
      (node (ref "U2") (pin "11") (pinfunction "SDO_11") (pintype "output"))
    )
    (net (code "13") (name "/TemperatureDAC1") (class "Default")
      (node (ref "J1") (pin "1") (pinfunction "1_1") (pintype "passive"))
      (node (ref "U1") (pin "22") (pinfunction "TEMPOUT_22") (pintype "output"))
    )
    (net (code "14") (name "/TemperatureDAC2") (class "Default")
      (node (ref "J3") (pin "1") (pinfunction "1_1") (pintype "passive"))
      (node (ref "U2") (pin "22") (pinfunction "TEMPOUT_22") (pintype "output"))
    )
    (net (code "15") (name "/Toggle0_1") (class "Default")
      (node (ref "R5") (pin "1") (pinfunction "1_1") (pintype "passive"))
      (node (ref "U1") (pin "15") (pinfunction "TOGGLE0_15") (pintype "input"))
    )
    (net (code "16") (name "/Toggle0_2") (class "Default")
      (node (ref "R13") (pin "1") (pinfunction "1_1") (pintype "passive"))
      (node (ref "U2") (pin "15") (pinfunction "TOGGLE0_15") (pintype "input"))
    )
    (net (code "17") (name "/Toggle1_1") (class "Default")
      (node (ref "R6") (pin "1") (pinfunction "1_1") (pintype "passive"))
      (node (ref "U1") (pin "16") (pinfunction "TOGGLE1_16") (pintype "input"))
    )
    (net (code "18") (name "/Toggle1_2") (class "Default")
      (node (ref "R15") (pin "1") (pinfunction "1_1") (pintype "passive"))
      (node (ref "U2") (pin "16") (pinfunction "TOGGLE1_16") (pintype "input"))
    )
    (net (code "19") (name "/Toggle2_1") (class "Default")
      (node (ref "R7") (pin "1") (pinfunction "1_1") (pintype "passive"))
      (node (ref "U1") (pin "17") (pinfunction "TOGGLE2_17") (pintype "input"))
    )
    (net (code "20") (name "/Toggle2_2") (class "Default")
      (node (ref "R16") (pin "1") (pinfunction "1_1") (pintype "passive"))
      (node (ref "U2") (pin "17") (pinfunction "TOGGLE2_17") (pintype "input"))
    )
    (net (code "21") (name "/Varactor Diode 0") (class "Default")
      (node (ref "TP0") (pin "1") (pinfunction "1_1") (pintype "passive"))
      (node (ref "U1") (pin "1") (pinfunction "OUT0_1") (pintype "output"))
      (node (ref "V0") (pin "1") (pinfunction "1_1") (pintype "passive"))
    )
    (net (code "22") (name "/Varactor Diode 1") (class "Default")
      (node (ref "TP1") (pin "1") (pinfunction "1_1") (pintype "passive"))
      (node (ref "U1") (pin "2") (pinfunction "OUT1_2") (pintype "output"))
      (node (ref "V1") (pin "1") (pinfunction "1_1") (pintype "passive"))
    )
    (net (code "23") (name "/Varactor Diode 2") (class "Default")
      (node (ref "TP2") (pin "1") (pinfunction "1_1") (pintype "passive"))
      (node (ref "U1") (pin "3") (pinfunction "OUT2_3") (pintype "output"))
      (node (ref "V2") (pin "1") (pinfunction "1_1") (pintype "passive"))
    )
    (net (code "24") (name "/Varactor Diode 3") (class "Default")
      (node (ref "TP3") (pin "1") (pinfunction "1_1") (pintype "passive"))
      (node (ref "U1") (pin "4") (pinfunction "OUT3_4") (pintype "output"))
      (node (ref "V3") (pin "1") (pinfunction "1_1") (pintype "passive"))
    )
    (net (code "25") (name "/Varactor Diode 4") (class "Default")
      (node (ref "TP4") (pin "1") (pinfunction "1_1") (pintype "passive"))
      (node (ref "U1") (pin "5") (pinfunction "OUT4_5") (pintype "output"))
      (node (ref "V4") (pin "1") (pinfunction "1_1") (pintype "passive"))
    )
    (net (code "26") (name "/Varactor Diode 5") (class "Default")
      (node (ref "TP5") (pin "1") (pinfunction "1_1") (pintype "passive"))
      (node (ref "U1") (pin "6") (pinfunction "OUT5_6") (pintype "output"))
      (node (ref "V5") (pin "1") (pinfunction "1_1") (pintype "passive"))
    )
    (net (code "27") (name "/Varactor Diode 6") (class "Default")
      (node (ref "TP6") (pin "1") (pinfunction "1_1") (pintype "passive"))
      (node (ref "U1") (pin "7") (pinfunction "OUT6_7") (pintype "output"))
      (node (ref "V6") (pin "1") (pinfunction "1_1") (pintype "passive"))
    )
    (net (code "28") (name "/Varactor Diode 7") (class "Default")
      (node (ref "TP7") (pin "1") (pinfunction "1_1") (pintype "passive"))
      (node (ref "U1") (pin "8") (pinfunction "OUT7_8") (pintype "output"))
      (node (ref "V7") (pin "1") (pinfunction "1_1") (pintype "passive"))
    )
    (net (code "29") (name "/Varactor Diode 8") (class "Default")
      (node (ref "TP8") (pin "1") (pinfunction "1_1") (pintype "passive"))
      (node (ref "U1") (pin "23") (pinfunction "OUT8_23") (pintype "output"))
      (node (ref "V8") (pin "1") (pinfunction "1_1") (pintype "passive"))
    )
    (net (code "30") (name "/Varactor Diode 9") (class "Default")
      (node (ref "TP9") (pin "1") (pinfunction "1_1") (pintype "passive"))
      (node (ref "U1") (pin "24") (pinfunction "OUT9_24") (pintype "output"))
      (node (ref "V9") (pin "1") (pinfunction "1_1") (pintype "passive"))
    )
    (net (code "31") (name "/Varactor Diode 10") (class "Default")
      (node (ref "TP10") (pin "1") (pinfunction "1_1") (pintype "passive"))
      (node (ref "U1") (pin "25") (pinfunction "OUT10_25") (pintype "output"))
      (node (ref "V10") (pin "1") (pinfunction "1_1") (pintype "passive"))
    )
    (net (code "32") (name "/Varactor Diode 11") (class "Default")
      (node (ref "TP11") (pin "1") (pinfunction "1_1") (pintype "passive"))
      (node (ref "U1") (pin "26") (pinfunction "OUT11_26") (pintype "output"))
      (node (ref "V11") (pin "1") (pinfunction "1_1") (pintype "passive"))
    )
    (net (code "33") (name "/Varactor Diode 12") (class "Default")
      (node (ref "TP12") (pin "1") (pinfunction "1_1") (pintype "passive"))
      (node (ref "U1") (pin "27") (pinfunction "OUT12_27") (pintype "output"))
      (node (ref "V12") (pin "1") (pinfunction "1_1") (pintype "passive"))
    )
    (net (code "34") (name "/Varactor Diode 13") (class "Default")
      (node (ref "TP13") (pin "1") (pinfunction "1_1") (pintype "passive"))
      (node (ref "U1") (pin "28") (pinfunction "OUT13_28") (pintype "output"))
      (node (ref "V13") (pin "1") (pinfunction "1_1") (pintype "passive"))
    )
    (net (code "35") (name "/Varactor Diode 14") (class "Default")
      (node (ref "TP14") (pin "1") (pinfunction "1_1") (pintype "passive"))
      (node (ref "U1") (pin "29") (pinfunction "OUT14_29") (pintype "output"))
      (node (ref "V14") (pin "1") (pinfunction "1_1") (pintype "passive"))
    )
    (net (code "36") (name "/Varactor Diode 15") (class "Default")
      (node (ref "TP15") (pin "1") (pinfunction "1_1") (pintype "passive"))
      (node (ref "U1") (pin "30") (pinfunction "OUT15_30") (pintype "output"))
      (node (ref "V15") (pin "1") (pinfunction "1_1") (pintype "passive"))
    )
    (net (code "37") (name "/Varactor Diode 16") (class "Default")
      (node (ref "TP16") (pin "1") (pinfunction "1_1") (pintype "passive"))
      (node (ref "U2") (pin "1") (pinfunction "OUT0_1") (pintype "output"))
      (node (ref "V16") (pin "1") (pinfunction "1_1") (pintype "passive"))
    )
    (net (code "38") (name "/Varactor Diode 17") (class "Default")
      (node (ref "TP17") (pin "1") (pinfunction "1_1") (pintype "passive"))
      (node (ref "U2") (pin "2") (pinfunction "OUT1_2") (pintype "output"))
      (node (ref "V17") (pin "1") (pinfunction "1_1") (pintype "passive"))
    )
    (net (code "39") (name "/Varactor Diode 18") (class "Default")
      (node (ref "TP18") (pin "1") (pinfunction "1_1") (pintype "passive"))
      (node (ref "U2") (pin "3") (pinfunction "OUT2_3") (pintype "output"))
      (node (ref "V18") (pin "1") (pinfunction "1_1") (pintype "passive"))
    )
    (net (code "40") (name "/Varactor Diode 19") (class "Default")
      (node (ref "TP19") (pin "1") (pinfunction "1_1") (pintype "passive"))
      (node (ref "U2") (pin "4") (pinfunction "OUT3_4") (pintype "output"))
      (node (ref "V19") (pin "1") (pinfunction "1_1") (pintype "passive"))
    )
    (net (code "41") (name "/Varactor Diode 20") (class "Default")
      (node (ref "TP20") (pin "1") (pinfunction "1_1") (pintype "passive"))
      (node (ref "U2") (pin "5") (pinfunction "OUT4_5") (pintype "output"))
      (node (ref "V20") (pin "1") (pinfunction "1_1") (pintype "passive"))
    )
    (net (code "42") (name "/Varactor Diode 21") (class "Default")
      (node (ref "TP21") (pin "1") (pinfunction "1_1") (pintype "passive"))
      (node (ref "U2") (pin "6") (pinfunction "OUT5_6") (pintype "output"))
      (node (ref "V21") (pin "1") (pinfunction "1_1") (pintype "passive"))
    )
    (net (code "43") (name "/Varactor Diode 22") (class "Default")
      (node (ref "TP22") (pin "1") (pinfunction "1_1") (pintype "passive"))
      (node (ref "U2") (pin "7") (pinfunction "OUT6_7") (pintype "output"))
      (node (ref "V22") (pin "1") (pinfunction "1_1") (pintype "passive"))
    )
    (net (code "44") (name "/Varactor Diode 23") (class "Default")
      (node (ref "TP23") (pin "1") (pinfunction "1_1") (pintype "passive"))
      (node (ref "U2") (pin "8") (pinfunction "OUT7_8") (pintype "output"))
      (node (ref "V23") (pin "1") (pinfunction "1_1") (pintype "passive"))
    )
    (net (code "45") (name "/Varactor Diode 24") (class "Default")
      (node (ref "TP24") (pin "1") (pinfunction "1_1") (pintype "passive"))
      (node (ref "U2") (pin "23") (pinfunction "OUT8_23") (pintype "output"))
      (node (ref "V24") (pin "1") (pinfunction "1_1") (pintype "passive"))
    )
    (net (code "46") (name "/Varactor Diode 25") (class "Default")
      (node (ref "TP25") (pin "1") (pinfunction "1_1") (pintype "passive"))
      (node (ref "U2") (pin "24") (pinfunction "OUT9_24") (pintype "output"))
      (node (ref "V25") (pin "1") (pinfunction "1_1") (pintype "passive"))
    )
    (net (code "47") (name "/Varactor Diode 26") (class "Default")
      (node (ref "TP26") (pin "1") (pinfunction "1_1") (pintype "passive"))
      (node (ref "U2") (pin "25") (pinfunction "OUT10_25") (pintype "output"))
      (node (ref "V26") (pin "1") (pinfunction "1_1") (pintype "passive"))
    )
    (net (code "48") (name "/Varactor Diode 27") (class "Default")
      (node (ref "TP27") (pin "1") (pinfunction "1_1") (pintype "passive"))
      (node (ref "U2") (pin "26") (pinfunction "OUT11_26") (pintype "output"))
      (node (ref "V27") (pin "1") (pinfunction "1_1") (pintype "passive"))
    )
    (net (code "49") (name "/Varactor Diode 28") (class "Default")
      (node (ref "TP28") (pin "1") (pinfunction "1_1") (pintype "passive"))
      (node (ref "U2") (pin "27") (pinfunction "OUT12_27") (pintype "output"))
      (node (ref "V28") (pin "1") (pinfunction "1_1") (pintype "passive"))
    )
    (net (code "50") (name "/Varactor Diode 29") (class "Default")
      (node (ref "TP29") (pin "1") (pinfunction "1_1") (pintype "passive"))
      (node (ref "U2") (pin "28") (pinfunction "OUT13_28") (pintype "output"))
      (node (ref "V29") (pin "1") (pinfunction "1_1") (pintype "passive"))
    )
    (net (code "51") (name "/Varactor Diode 30") (class "Default")
      (node (ref "TP30") (pin "1") (pinfunction "1_1") (pintype "passive"))
      (node (ref "U2") (pin "29") (pinfunction "OUT14_29") (pintype "output"))
      (node (ref "V30") (pin "1") (pinfunction "1_1") (pintype "passive"))
    )
    (net (code "52") (name "/Varactor Diode 31") (class "Default")
      (node (ref "TP31") (pin "1") (pinfunction "1_1") (pintype "passive"))
      (node (ref "U2") (pin "30") (pinfunction "OUT15_30") (pintype "output"))
      (node (ref "V31") (pin "1") (pinfunction "1_1") (pintype "passive"))
    )
    (net (code "53") (name "GND") (class "Default")
      (node (ref "C1") (pin "2") (pinfunction "2_2") (pintype "passive"))
      (node (ref "C10") (pin "2") (pinfunction "2_2") (pintype "passive"))
      (node (ref "C11") (pin "2") (pinfunction "2_2") (pintype "passive"))
      (node (ref "C13") (pin "2") (pinfunction "2_2") (pintype "passive"))
      (node (ref "C14") (pin "2") (pinfunction "2_2") (pintype "passive"))
      (node (ref "C15") (pin "2") (pinfunction "2_2") (pintype "passive"))
      (node (ref "C16") (pin "2") (pinfunction "2_2") (pintype "passive"))
      (node (ref "C18") (pin "2") (pinfunction "2_2") (pintype "passive"))
      (node (ref "C19") (pin "2") (pinfunction "2_2") (pintype "passive"))
      (node (ref "C2") (pin "2") (pinfunction "2_2") (pintype "passive"))
      (node (ref "C20") (pin "2") (pinfunction "2_2") (pintype "passive"))
      (node (ref "C21") (pin "2") (pinfunction "2_2") (pintype "passive"))
      (node (ref "C22") (pin "2") (pinfunction "2_2") (pintype "passive"))
      (node (ref "C23") (pin "2") (pinfunction "2_2") (pintype "passive"))
      (node (ref "C24") (pin "2") (pinfunction "2_2") (pintype "passive"))
      (node (ref "C25") (pin "2") (pinfunction "2_2") (pintype "passive"))
      (node (ref "C26") (pin "2") (pinfunction "2_2") (pintype "passive"))
      (node (ref "C3") (pin "2") (pinfunction "2_2") (pintype "passive"))
      (node (ref "C4") (pin "2") (pinfunction "2_2") (pintype "passive"))
      (node (ref "C5") (pin "2") (pinfunction "2_2") (pintype "passive"))
      (node (ref "C6") (pin "2") (pinfunction "2_2") (pintype "passive"))
      (node (ref "C7") (pin "2") (pinfunction "2_2") (pintype "passive"))
      (node (ref "C8") (pin "2") (pinfunction "2_2") (pintype "passive"))
      (node (ref "C9") (pin "2") (pinfunction "2_2") (pintype "passive"))
      (node (ref "IC1") (pin "3") (pinfunction "GND_3") (pintype "passive"))
      (node (ref "IC1") (pin "7") (pinfunction "EP_7") (pintype "passive"))
      (node (ref "IC2") (pin "3") (pinfunction "GND_3") (pintype "passive"))
      (node (ref "IC2") (pin "7") (pinfunction "EP_7") (pintype "passive"))
      (node (ref "J4") (pin "4") (pinfunction "4_4") (pintype "passive"))
      (node (ref "R13") (pin "2") (pinfunction "2_2") (pintype "passive"))
      (node (ref "R15") (pin "2") (pinfunction "2_2") (pintype "passive"))
      (node (ref "R16") (pin "2") (pinfunction "2_2") (pintype "passive"))
      (node (ref "R17") (pin "1") (pinfunction "1_1") (pintype "passive"))
      (node (ref "R20") (pin "1") (pinfunction "1_1") (pintype "passive"))
      (node (ref "R5") (pin "2") (pinfunction "2_2") (pintype "passive"))
      (node (ref "R6") (pin "2") (pinfunction "2_2") (pintype "passive"))
      (node (ref "R7") (pin "2") (pinfunction "2_2") (pintype "passive"))
      (node (ref "U1") (pin "10") (pinfunction "GND_10") (pintype "power_in"))
      (node (ref "U1") (pin "32") (pinfunction "VSS_32") (pintype "power_in"))
      (node (ref "U1") (pin "35") (pinfunction "REFGND_35") (pintype "power_in"))
      (node (ref "U1") (pin "36") (pinfunction "GND_36") (pintype "power_in"))
      (node (ref "U1") (pin "39") (pinfunction "VSS_39") (pintype "power_in"))
      (node (ref "U1") (pin "41") (pinfunction "EXP_41") (pintype "power_in"))
      (node (ref "U2") (pin "10") (pinfunction "GND_10") (pintype "power_in"))
      (node (ref "U2") (pin "32") (pinfunction "VSS_32") (pintype "power_in"))
      (node (ref "U2") (pin "35") (pinfunction "REFGND_35") (pintype "power_in"))
      (node (ref "U2") (pin "36") (pinfunction "GND_36") (pintype "power_in"))
      (node (ref "U2") (pin "39") (pinfunction "VSS_39") (pintype "power_in"))
      (node (ref "U2") (pin "41") (pinfunction "EXP_41") (pintype "power_in"))
      (node (ref "V0") (pin "2") (pinfunction "2_2") (pintype "passive"))
      (node (ref "V1") (pin "2") (pinfunction "2_2") (pintype "passive"))
      (node (ref "V10") (pin "2") (pinfunction "2_2") (pintype "passive"))
      (node (ref "V11") (pin "2") (pinfunction "2_2") (pintype "passive"))
      (node (ref "V12") (pin "2") (pinfunction "2_2") (pintype "passive"))
      (node (ref "V13") (pin "2") (pinfunction "2_2") (pintype "passive"))
      (node (ref "V14") (pin "2") (pinfunction "2_2") (pintype "passive"))
      (node (ref "V15") (pin "2") (pinfunction "2_2") (pintype "passive"))
      (node (ref "V16") (pin "2") (pinfunction "2_2") (pintype "passive"))
      (node (ref "V17") (pin "2") (pinfunction "2_2") (pintype "passive"))
      (node (ref "V18") (pin "2") (pinfunction "2_2") (pintype "passive"))
      (node (ref "V19") (pin "2") (pinfunction "2_2") (pintype "passive"))
      (node (ref "V2") (pin "2") (pinfunction "2_2") (pintype "passive"))
      (node (ref "V20") (pin "2") (pinfunction "2_2") (pintype "passive"))
      (node (ref "V21") (pin "2") (pinfunction "2_2") (pintype "passive"))
      (node (ref "V22") (pin "2") (pinfunction "2_2") (pintype "passive"))
      (node (ref "V23") (pin "2") (pinfunction "2_2") (pintype "passive"))
      (node (ref "V24") (pin "2") (pinfunction "2_2") (pintype "passive"))
      (node (ref "V25") (pin "2") (pinfunction "2_2") (pintype "passive"))
      (node (ref "V26") (pin "2") (pinfunction "2_2") (pintype "passive"))
      (node (ref "V27") (pin "2") (pinfunction "2_2") (pintype "passive"))
      (node (ref "V28") (pin "2") (pinfunction "2_2") (pintype "passive"))
      (node (ref "V29") (pin "2") (pinfunction "2_2") (pintype "passive"))
      (node (ref "V3") (pin "2") (pinfunction "2_2") (pintype "passive"))
      (node (ref "V30") (pin "2") (pinfunction "2_2") (pintype "passive"))
      (node (ref "V31") (pin "2") (pinfunction "2_2") (pintype "passive"))
      (node (ref "V4") (pin "2") (pinfunction "2_2") (pintype "passive"))
      (node (ref "V5") (pin "2") (pinfunction "2_2") (pintype "passive"))
      (node (ref "V6") (pin "2") (pinfunction "2_2") (pintype "passive"))
      (node (ref "V7") (pin "2") (pinfunction "2_2") (pintype "passive"))
      (node (ref "V8") (pin "2") (pinfunction "2_2") (pintype "passive"))
      (node (ref "V9") (pin "2") (pinfunction "2_2") (pintype "passive"))
    )
    (net (code "54") (name "Net-(IC1-NC{slash}ADJ)") (class "Default")
      (node (ref "C12") (pin "2") (pinfunction "2_2") (pintype "passive"))
      (node (ref "IC1") (pin "2") (pinfunction "NC/ADJ_2") (pintype "passive"))
      (node (ref "R14") (pin "1") (pinfunction "1_1") (pintype "passive"))
      (node (ref "R17") (pin "2") (pinfunction "2_2") (pintype "passive"))
    )
    (net (code "55") (name "Net-(IC2-NC{slash}ADJ)") (class "Default")
      (node (ref "C17") (pin "2") (pinfunction "2_2") (pintype "passive"))
      (node (ref "IC2") (pin "2") (pinfunction "NC/ADJ_2") (pintype "passive"))
      (node (ref "R19") (pin "1") (pinfunction "1_1") (pintype "passive"))
      (node (ref "R20") (pin "2") (pinfunction "2_2") (pintype "passive"))
    )
    (net (code "56") (name "Net-(U1-REF)") (class "Default")
      (node (ref "C1") (pin "1") (pinfunction "1_1") (pintype "passive"))
      (node (ref "U1") (pin "33") (pinfunction "REF_33") (pintype "bidirectional"))
    )
    (net (code "57") (name "Net-(U1-REFCMP)") (class "Default")
      (node (ref "C2") (pin "1") (pinfunction "1_1") (pintype "passive"))
      (node (ref "U1") (pin "34") (pinfunction "REFCMP_34") (pintype "bidirectional"))
    )
    (net (code "58") (name "Net-(U1-~{CLR})") (class "Default")
      (node (ref "R1") (pin "1") (pinfunction "1_1") (pintype "passive"))
      (node (ref "Test2") (pin "1") (pinfunction "1_1") (pintype "passive"))
      (node (ref "U1") (pin "20") (pinfunction "~{CLR}_20") (pintype "input"))
    )
    (net (code "59") (name "Net-(U1-~{LDAC})") (class "Default")
      (node (ref "R2") (pin "1") (pinfunction "1_1") (pintype "passive"))
      (node (ref "Test3") (pin "1") (pinfunction "1_1") (pintype "passive"))
      (node (ref "U1") (pin "18") (pinfunction "~{LDAC}_18") (pintype "input"))
    )
    (net (code "60") (name "Net-(U1-~{RESET})") (class "Default")
      (node (ref "R3") (pin "1") (pinfunction "1_1") (pintype "passive"))
      (node (ref "Test1") (pin "1") (pinfunction "1_1") (pintype "passive"))
      (node (ref "U1") (pin "19") (pinfunction "~{RESET}_19") (pintype "input"))
    )
    (net (code "61") (name "Net-(U2-REF)") (class "Default")
      (node (ref "C14") (pin "1") (pinfunction "1_1") (pintype "passive"))
      (node (ref "U2") (pin "33") (pinfunction "REF_33") (pintype "bidirectional"))
    )
    (net (code "62") (name "Net-(U2-REFCMP)") (class "Default")
      (node (ref "C15") (pin "1") (pinfunction "1_1") (pintype "passive"))
      (node (ref "U2") (pin "34") (pinfunction "REFCMP_34") (pintype "bidirectional"))
    )
    (net (code "63") (name "Net-(U2-~{CLR})") (class "Default")
      (node (ref "R8") (pin "1") (pinfunction "1_1") (pintype "passive"))
      (node (ref "Test5") (pin "1") (pinfunction "1_1") (pintype "passive"))
      (node (ref "U2") (pin "20") (pinfunction "~{CLR}_20") (pintype "input"))
    )
    (net (code "64") (name "Net-(U2-~{LDAC})") (class "Default")
      (node (ref "R9") (pin "1") (pinfunction "1_1") (pintype "passive"))
      (node (ref "Test6") (pin "1") (pinfunction "1_1") (pintype "passive"))
      (node (ref "U2") (pin "18") (pinfunction "~{LDAC}_18") (pintype "input"))
    )
    (net (code "65") (name "Net-(U2-~{RESET})") (class "Default")
      (node (ref "R10") (pin "1") (pinfunction "1_1") (pintype "passive"))
      (node (ref "Test4") (pin "1") (pinfunction "1_1") (pintype "passive"))
      (node (ref "U2") (pin "19") (pinfunction "~{RESET}_19") (pintype "input"))
    )
  )
)
